# homecomputer-6502.net
KiCad netlist of a schematic drawn in EAGLE
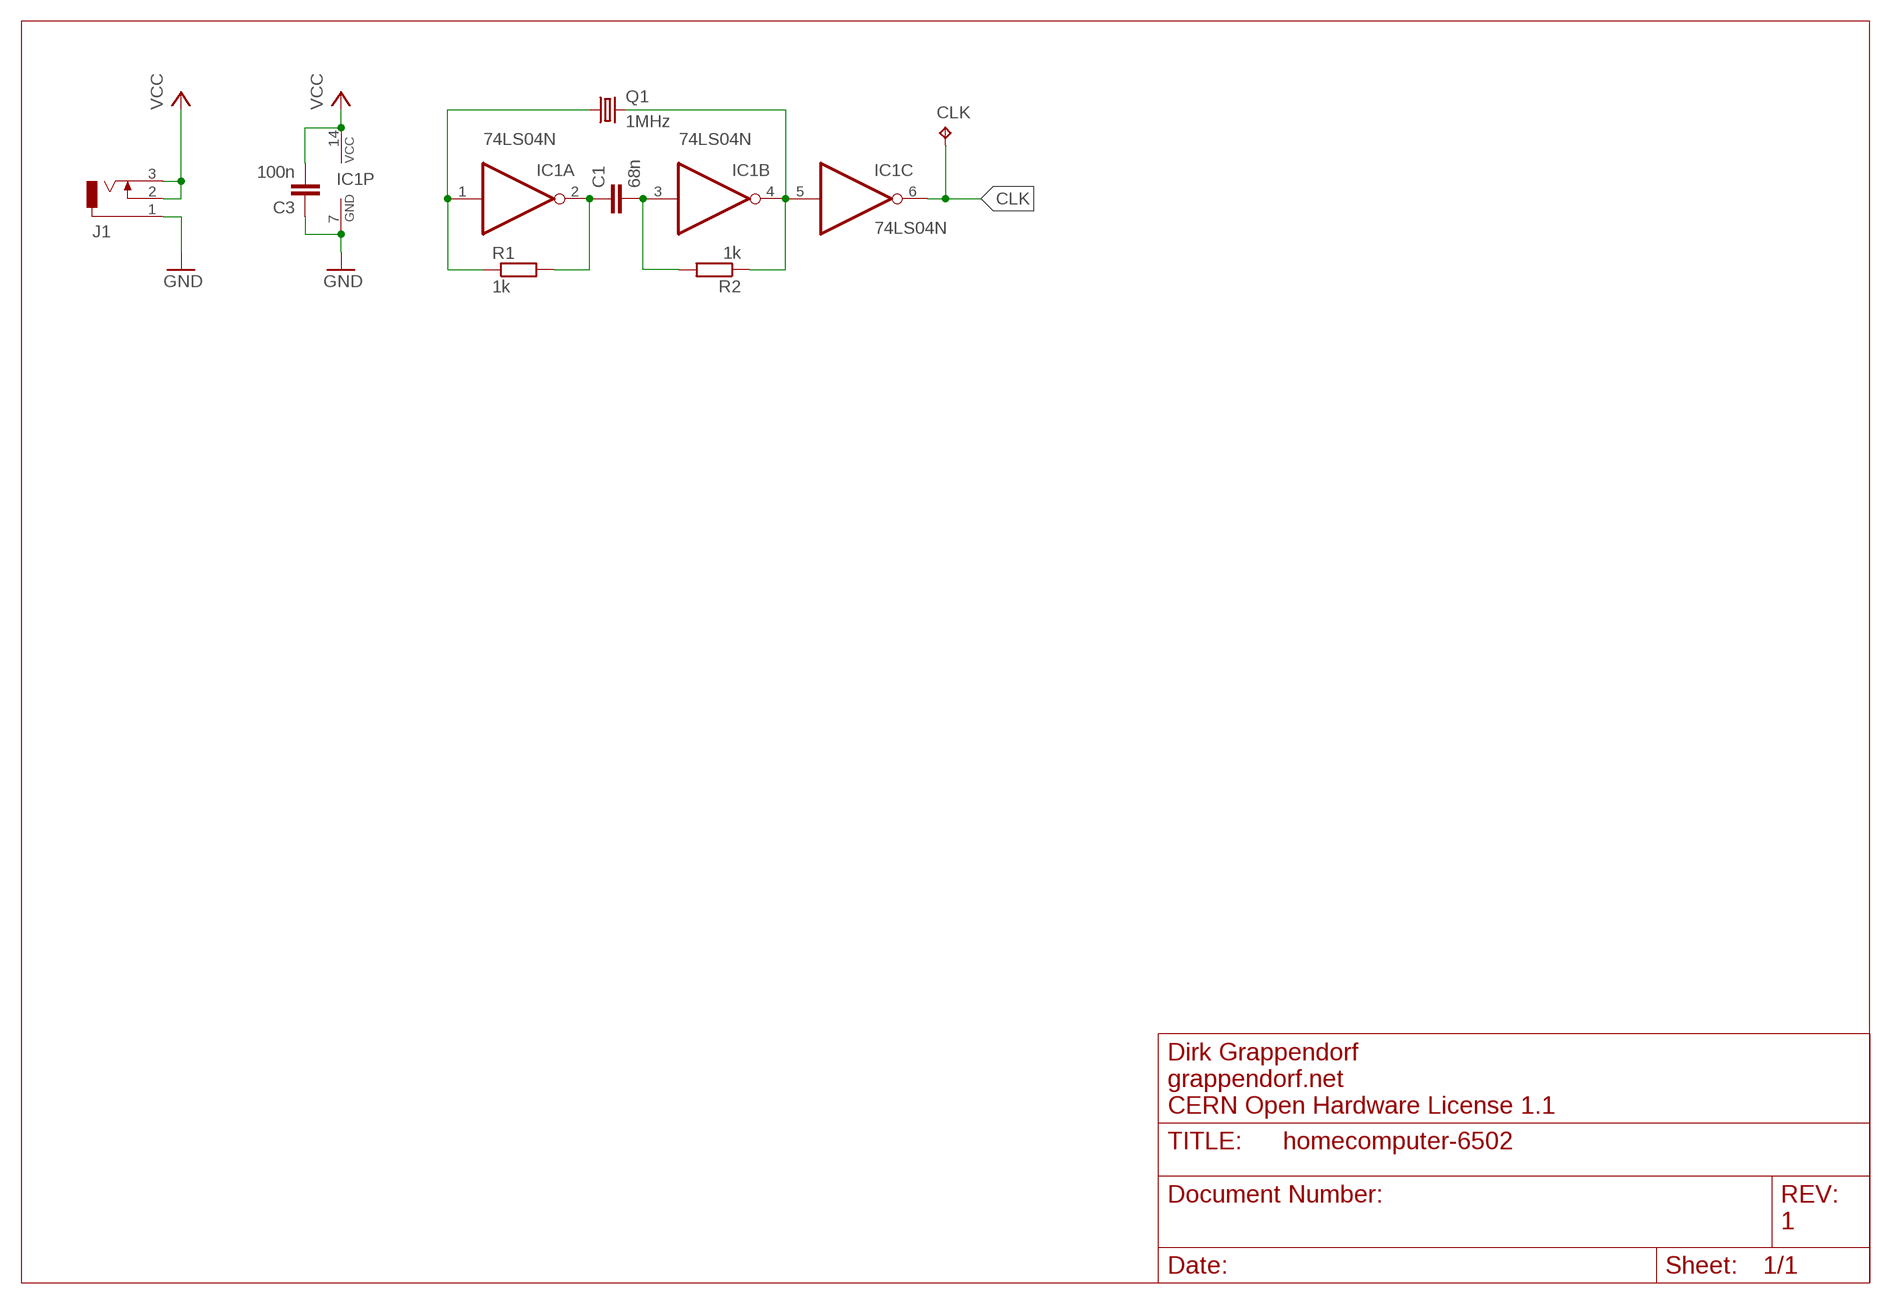
[diagram p0: schematic, sheet 1]

(export (version "E")
  (design (tool "Eeschema 10.0.6"))
  (components
    (comp (ref "C1")
      (value "68n")
      (footprint "eagle-import:C025-024X044")
      (libsource (lib "eagle-import") (part "C-EU025-024X044"))
    )
    (comp (ref "C3")
      (value "100n")
      (footprint "eagle-import:C025-024X044")
      (libsource (lib "eagle-import") (part "C-EU025-024X044"))
    )
    (comp (ref "CLK")
      (value "TPTP15SQ")
      (footprint "eagle-import:TP15SQ")
      (libsource (lib "eagle-import") (part "TPTP15SQ"))
    )
    (comp (ref "IC1")
      (value "74LS04N")
      (footprint "eagle-import:DIL14")
      (libsource (lib "eagle-import") (part "7404NLS"))
    )
    (comp (ref "J1")
      (value "DCJ0303")
      (footprint "eagle-import:DCJ0303")
      (libsource (lib "eagle-import") (part "DCJ0303"))
    )
    (comp (ref "Q1")
      (value "1MHz")
      (footprint "eagle-import:HC49U-V")
      (libsource (lib "eagle-import") (part "CRYSTALHC49U-V"))
    )
    (comp (ref "R1")
      (value "1k")
      (footprint "eagle-import:0204_5")
      (libsource (lib "eagle-import") (part "R-EU_0204/5"))
    )
    (comp (ref "R2")
      (value "1k")
      (footprint "eagle-import:0204_5")
      (libsource (lib "eagle-import") (part "R-EU_0204/5"))
    )
  )
  (nets
    (net (code "1") (name "CLK") (class "Default")
      (node (ref "CLK") (pin "TP") (pinfunction "TP_TP") (pintype "input"))
      (node (ref "IC1") (pin "6") (pinfunction "O_6") (pintype "output"))
    )
    (net (code "2") (name "GND") (class "Default")
      (node (ref "C3") (pin "1") (pinfunction "1_1") (pintype "passive"))
      (node (ref "IC1") (pin "7") (pinfunction "GND_7") (pintype "power_in"))
      (node (ref "J1") (pin "1") (pinfunction "1_1") (pintype "passive"))
    )
    (net (code "3") (name "Net-(IC1A-I)") (class "Default")
      (node (ref "IC1") (pin "1") (pinfunction "I_1") (pintype "input"))
      (node (ref "Q1") (pin "1") (pinfunction "1_1") (pintype "passive"))
      (node (ref "R1") (pin "1") (pinfunction "1_1") (pintype "passive"))
    )
    (net (code "4") (name "Net-(IC1A-O)") (class "Default")
      (node (ref "C1") (pin "1") (pinfunction "1_1") (pintype "passive"))
      (node (ref "IC1") (pin "2") (pinfunction "O_2") (pintype "output"))
      (node (ref "R1") (pin "2") (pinfunction "2_2") (pintype "passive"))
    )
    (net (code "5") (name "Net-(IC1B-I)") (class "Default")
      (node (ref "C1") (pin "2") (pinfunction "2_2") (pintype "passive"))
      (node (ref "IC1") (pin "3") (pinfunction "I_3") (pintype "input"))
      (node (ref "R2") (pin "2") (pinfunction "2_2") (pintype "passive"))
    )
    (net (code "6") (name "Net-(IC1B-O)") (class "Default")
      (node (ref "IC1") (pin "4") (pinfunction "O_4") (pintype "output"))
      (node (ref "IC1") (pin "5") (pinfunction "I_5") (pintype "input"))
      (node (ref "Q1") (pin "2") (pinfunction "2_2") (pintype "passive"))
      (node (ref "R2") (pin "1") (pinfunction "1_1") (pintype "passive"))
    )
    (net (code "7") (name "VCC") (class "Default")
      (node (ref "C3") (pin "2") (pinfunction "2_2") (pintype "passive"))
      (node (ref "IC1") (pin "14") (pinfunction "VCC_14") (pintype "power_in"))
      (node (ref "J1") (pin "2") (pinfunction "2_2") (pintype "passive"))
      (node (ref "J1") (pin "3") (pinfunction "3_3") (pintype "passive"))
    )
  )
)
